# P03_MPU2_Comm.net
KiCad netlist of a schematic drawn in Altium Designer
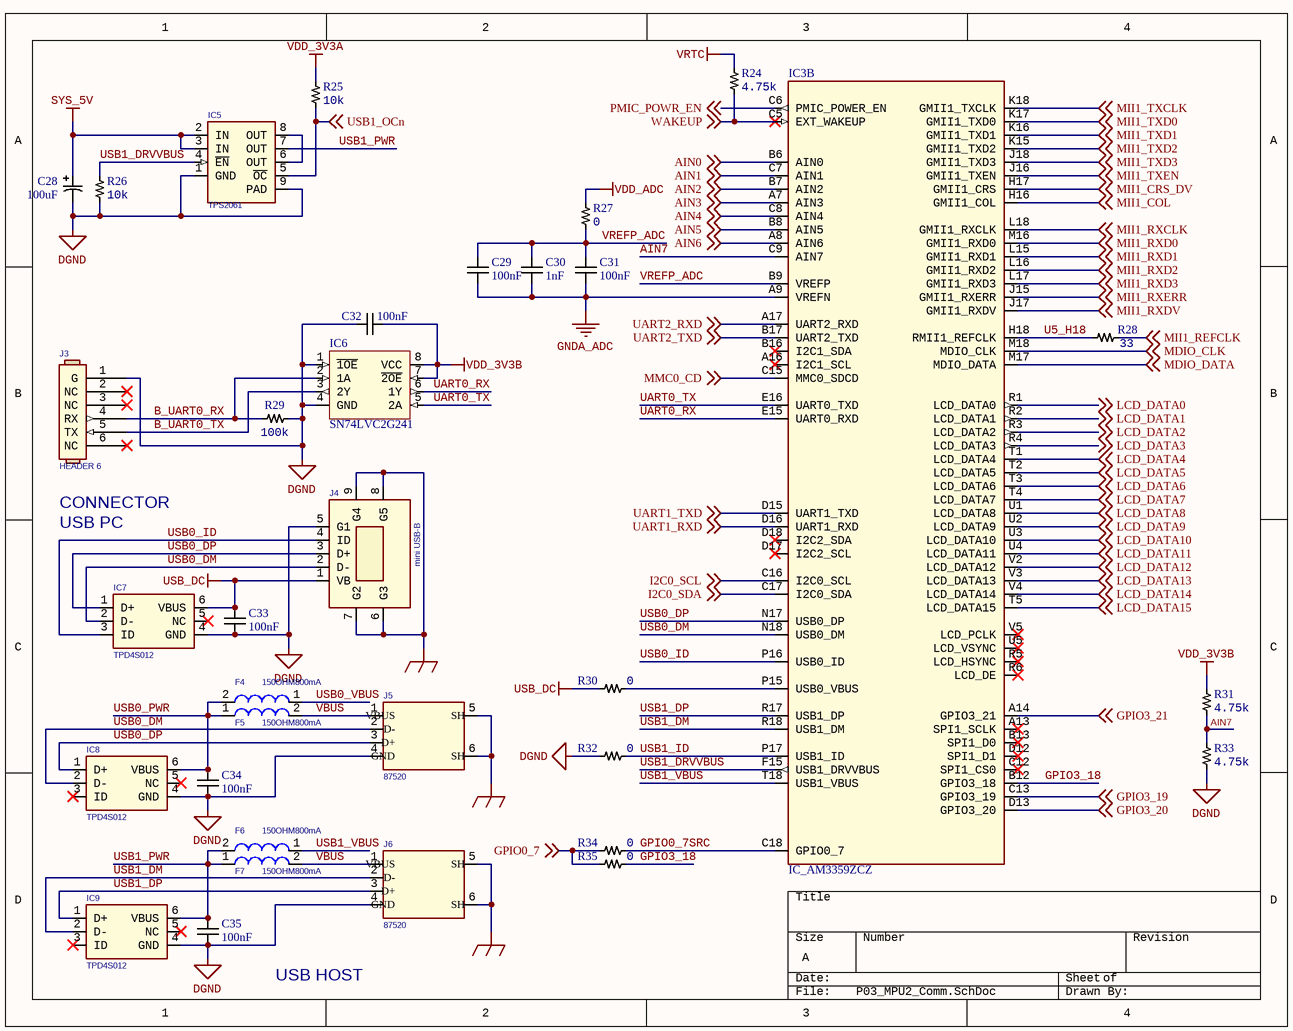
[diagram p0: P03_MPU2_Comm.SchDoc]

(export (version "E")
  (design (tool "Eeschema 10.0.6"))
  (components
    (comp (ref "C28")
      (value "EEE-0JA101SP")
      (footprint "Orient:CAP6.6x6.6")
      (description "POL CAP 100uF SMD")
      (fields
        (field (name "MANUFACTURER") "Panasonic")
        (field (name "TOLERANCE") "20%")
        (field (name "CAPACITANCE") "100uF")
      )
      (libsource (lib "Orient") (part "CAP_POL_100uF"))
    )
    (comp (ref "C29")
      (value "C0402C104K4RACTU")
      (footprint "Orient:CAP0402")
      (description "MLCC 100nF 0402 SMD")
      (fields
        (field (name "MANUFACTURER") "KEMET")
        (field (name "CAPACITANCE") "100nF")
        (field (name "TOLERANCE") "10%")
      )
      (libsource (lib "Orient") (part "CAP_100nF"))
    )
    (comp (ref "C30")
      (value "CC0402KRX7R9BB102")
      (footprint "Orient:CAP0402")
      (description "MLCC 1nF 0402 SMD")
      (fields
        (field (name "MANUFACTURER") "Yageo")
        (field (name "CAPACITANCE") "1nF")
        (field (name "TOLERANCE") "10%")
      )
      (libsource (lib "Orient") (part "CAP_1nF"))
    )
    (comp (ref "C31")
      (value "C0402C104K4RACTU")
      (footprint "Orient:CAP0402")
      (description "MLCC 100nF 0402 SMD")
      (fields
        (field (name "MANUFACTURER") "KEMET")
        (field (name "CAPACITANCE") "100nF")
        (field (name "TOLERANCE") "10%")
      )
      (libsource (lib "Orient") (part "CAP_100nF"))
    )
    (comp (ref "C32")
      (value "C0402C104K4RACTU")
      (footprint "Orient:CAP0402")
      (description "MLCC 100nF 0402 SMD")
      (fields
        (field (name "MANUFACTURER") "KEMET")
        (field (name "CAPACITANCE") "100nF")
        (field (name "TOLERANCE") "10%")
      )
      (libsource (lib "Orient") (part "CAP_100nF"))
    )
    (comp (ref "C33")
      (value "C0402C104K4RACTU")
      (footprint "Orient:CAP0402")
      (description "MLCC 100nF 0402 SMD")
      (fields
        (field (name "MANUFACTURER") "KEMET")
        (field (name "CAPACITANCE") "100nF")
        (field (name "TOLERANCE") "10%")
      )
      (libsource (lib "Orient") (part "CAP_100nF"))
    )
    (comp (ref "C34")
      (value "C0402C104K4RACTU")
      (footprint "Orient:CAP0402")
      (description "MLCC 100nF 0402 SMD")
      (fields
        (field (name "MANUFACTURER") "KEMET")
        (field (name "CAPACITANCE") "100nF")
        (field (name "TOLERANCE") "10%")
      )
      (libsource (lib "Orient") (part "CAP_100nF"))
    )
    (comp (ref "C35")
      (value "C0402C104K4RACTU")
      (footprint "Orient:CAP0402")
      (description "MLCC 100nF 0402 SMD")
      (fields
        (field (name "MANUFACTURER") "KEMET")
        (field (name "CAPACITANCE") "100nF")
        (field (name "TOLERANCE") "10%")
      )
      (libsource (lib "Orient") (part "CAP_100nF"))
    )
    (comp (ref "F4")
      (value "150OHM800mA")
      (footprint "Orient:FB0805")
      (description "FERRITE 800MA 150 OHM 0805 SMD")
      (fields
        (field (name "MANUFACTURER") "Laird-Signal Integrity Products")
        (field (name "MANUFACTURER PART NUMBER") "LI0805H151R-10")
      )
      (libsource (lib "Orient") (part "FERR"))
    )
    (comp (ref "F5")
      (value "150OHM800mA")
      (footprint "Orient:FB0805")
      (description "FERRITE 800MA 150 OHM 0805 SMD")
      (fields (field (name "MFR") "Steward") (field (name "TIINTPARTNUMBER") "1L0010"))
      (libsource (lib "") (part "FERR_1"))
    )
    (comp (ref "F6")
      (value "150OHM800mA")
      (footprint "Orient:FB0805")
      (description "FERRITE 800MA 150 OHM 0805 SMD")
      (fields
        (field (name "MANUFACTURER") "Laird-Signal Integrity Products")
        (field (name "MANUFACTURER PART NUMBER") "LI0805H151R-10")
      )
      (libsource (lib "Orient") (part "FERR"))
    )
    (comp (ref "F7")
      (value "150OHM800mA")
      (footprint "Orient:FB0805")
      (description "FERRITE 800MA 150 OHM 0805 SMD")
      (fields (field (name "MFR") "Steward") (field (name "TIINTPARTNUMBER") "1L0010"))
      (libsource (lib "") (part "FERR_1"))
    )
    (comp (ref "IC3")
      (value "IC_AM3359ZCZ")
      (footprint "Orient:BGA-324")
      (description "SubArctic Cortex A8 Processor 18x18")
      (fields
        (field (name "MANUFACTURER") "Texas Instruments")
        (field (name "MANUFACTURER PART NUMBER") "XAM3359ZCZ")
      )
      (libsource (lib "Orient") (part "IC_AM335X_ZCE_1"))
    )
    (comp (ref "IC5")
      (value "TPS2061")
      (footprint "Orient:HVSSOP-8")
      (description "IC 1.5A PWR DIST SWITCH 8-SOIC")
      (fields
        (field (name "MANUFACTURER") "Texas Instruments")
        (field (name "MANUFACTURER PART NUMBER") "TPS2051BDGNR")
      )
      (libsource (lib "Orient") (part "TPS2061"))
    )
    (comp (ref "IC6")
      (value "SN74LVC2G241")
      (footprint "Orient:VSSOP-8")
      (description "IC BUFF/DVR TRI-ST DL 8VSSOP")
      (fields
        (field (name "MANUFACTURER") "Texas Instruments")
        (field (name "MANUFACTURER PART NUMBER") "SN74LVC2G241DCUR")
      )
      (libsource (lib "Orient") (part "SN74LVC2G241"))
    )
    (comp (ref "IC7")
      (value "TPD4S012")
      (footprint "Orient:U_6_DRY")
      (description "ESD 4channel USB Interface")
      (fields (field (name "MFR") "TI") (field (name "TIINTPARTNUMBER") "1A0233"))
      (libsource (lib "Orient") (part "PROT_TPD4S012"))
    )
    (comp (ref "IC8")
      (value "TPD4S012")
      (footprint "Orient:U_6_DRY")
      (description "ESD 4channel USB Interface")
      (fields (field (name "MFR") "TI") (field (name "TIINTPARTNUMBER") "1A0233"))
      (libsource (lib "Orient") (part "PROT_TPD4S012"))
    )
    (comp (ref "IC9")
      (value "TPD4S012")
      (footprint "Orient:U_6_DRY")
      (description "ESD 4channel USB Interface")
      (fields (field (name "MFR") "TI") (field (name "TIINTPARTNUMBER") "1A0233"))
      (libsource (lib "Orient") (part "PROT_TPD4S012"))
    )
    (comp (ref "J3")
      (value "HEADER 6")
      (footprint "Orient:SIP6")
      (description "CONN HEADER 6POS, VERTICAL,  .100 STR TIN")
      (fields
        (field (name "MANUFACTURER") "Samtec Inc")
        (field (name "MANUFACTURER PART NUMBER") "FTR-110-03-G-D-06")
      )
      (libsource (lib "Orient") (part "HDR_6x1"))
    )
    (comp (ref "J4")
      (value "mini USB-B")
      (footprint "Orient:USB5MINI_4SHIELDED_SMD-5")
      (description "CONN RCPT USB MINI B R/A SMD")
      (fields (field (name "MANUFACTURER") "KYCON") (field (name "MANUFACTURER PART NUMBER") "0565790576"))
      (libsource (lib "Orient") (part "MINI-USB-AB-SOCKET"))
    )
    (comp (ref "J5")
      (value "87520")
      (footprint "Orient:USB_A")
      (description "CONN RCPT USB TYPE A R/A PCB")
      (fields (field (name "MANUFACTURER") "FCI") (field (name "MANUFACTURER PART NUMBER") "87520-0010BLF"))
      (libsource (lib "Orient") (part "CONN_USBA"))
    )
    (comp (ref "J6")
      (value "87520")
      (footprint "Orient:USB_A")
      (description "CONN RCPT USB TYPE A R/A PCB")
      (fields (field (name "MANUFACTURER") "FCI") (field (name "MANUFACTURER PART NUMBER") "87520-0010BLF"))
      (libsource (lib "Orient") (part "CONN_USBA"))
    )
    (comp (ref "R24")
      (value "RC0402FR-074K75L")
      (footprint "Orient:RES0402")
      (description "Resistor 4.75kOhm 0402 SMD")
      (fields
        (field (name "MANUFACTURER") "Yageo")
        (field (name "TOLERANCE") "1%")
        (field (name "RESISTANCE") "4.75k")
      )
      (libsource (lib "Orient") (part "RES_4.75k"))
    )
    (comp (ref "R25")
      (value "RC0402FR-0710KL")
      (footprint "Orient:RES0402")
      (description "Resistor 10kOhm 0402 SMD")
      (fields
        (field (name "MANUFACTURER") "Yageo")
        (field (name "TOLERANCE") "1%")
        (field (name "RESISTANCE") "10k")
      )
      (libsource (lib "Orient") (part "RES_10k"))
    )
    (comp (ref "R26")
      (value "RC0402FR-0710KL")
      (footprint "Orient:RES0402")
      (description "Resistor 10kOhm 0402 SMD")
      (fields
        (field (name "MANUFACTURER") "Yageo")
        (field (name "TOLERANCE") "1%")
        (field (name "RESISTANCE") "10k")
      )
      (libsource (lib "Orient") (part "RES_10k"))
    )
    (comp (ref "R27")
      (value "RC0402JR-070RL")
      (footprint "Orient:RES0402")
      (description "Resistor 0Ohm 0402 SMD")
      (fields
        (field (name "MANUFACTURER") "Yageo")
        (field (name "TOLERANCE") "5%")
        (field (name "RESISTANCE") "0")
      )
      (libsource (lib "Orient") (part "RES_0"))
    )
    (comp (ref "R28")
      (value "RC0402FR-0733RL")
      (footprint "Orient:RES0402")
      (description "Resistor 33Ohm 0402 SMD")
      (fields
        (field (name "MANUFACTURER") "Yageo")
        (field (name "TOLERANCE") "1%")
        (field (name "RESISTANCE") "33")
      )
      (libsource (lib "Orient") (part "RES_33"))
    )
    (comp (ref "R29")
      (value "RC0402FR-07100KL")
      (footprint "Orient:RES0402")
      (description "Resistor 100kOhm 0402 SMD")
      (fields
        (field (name "MANUFACTURER") "Yageo")
        (field (name "TOLERANCE") "1%")
        (field (name "RESISTANCE") "100k")
      )
      (libsource (lib "Orient") (part "RES_100k"))
    )
    (comp (ref "R30")
      (value "RC0402JR-070RL")
      (footprint "Orient:RES0402")
      (description "Resistor 0Ohm 0402 SMD")
      (fields
        (field (name "MANUFACTURER") "Yageo")
        (field (name "TOLERANCE") "5%")
        (field (name "RESISTANCE") "0")
      )
      (libsource (lib "Orient") (part "RES_0"))
    )
    (comp (ref "R31")
      (value "RC0402FR-074K75L")
      (footprint "Orient:RES0402")
      (description "Resistor 4.75kOhm 0402 SMD")
      (fields
        (field (name "MANUFACTURER") "Yageo")
        (field (name "TOLERANCE") "1%")
        (field (name "RESISTANCE") "4.75k")
      )
      (libsource (lib "Orient") (part "RES_4.75k"))
    )
    (comp (ref "R32")
      (value "RC0402JR-070RL")
      (footprint "Orient:RES0402")
      (description "Resistor 0Ohm 0402 SMD")
      (fields
        (field (name "MANUFACTURER") "Yageo")
        (field (name "TOLERANCE") "5%")
        (field (name "RESISTANCE") "0")
      )
      (libsource (lib "Orient") (part "RES_0"))
    )
    (comp (ref "R33")
      (value "RC0402FR-074K75L")
      (footprint "Orient:RES0402")
      (description "Resistor 4.75kOhm 0402 SMD")
      (fields
        (field (name "MANUFACTURER") "Yageo")
        (field (name "TOLERANCE") "1%")
        (field (name "RESISTANCE") "4.75k")
      )
      (libsource (lib "Orient") (part "RES_4.75k"))
    )
    (comp (ref "R34")
      (value "RC0402JR-070RL")
      (footprint "Orient:RES0402")
      (description "Resistor 0Ohm 0402 SMD")
      (fields
        (field (name "MANUFACTURER") "Yageo")
        (field (name "TOLERANCE") "5%")
        (field (name "RESISTANCE") "0")
      )
      (libsource (lib "Orient") (part "RES_0"))
    )
    (comp (ref "R35")
      (value "RC0402JR-070RL")
      (footprint "Orient:RES0402")
      (description "Resistor 0Ohm 0402 SMD")
      (fields
        (field (name "MANUFACTURER") "Yageo")
        (field (name "TOLERANCE") "5%")
        (field (name "RESISTANCE") "0")
      )
      (libsource (lib "Orient") (part "RES_0"))
    )
  )
  (nets
    (net (code "1") (name "/AIN7") (class "Default")
      (node (ref "IC3") (pin "C9") (pinfunction "AIN7_C9") (pintype "passive"))
      (node (ref "R31") (pin "1") (pintype "passive"))
      (node (ref "R33") (pin "2") (pintype "passive"))
    )
    (net (code "2") (name "/B_UART0_RX") (class "Default")
      (node (ref "IC6") (pin "2") (pinfunction "1A_2") (pintype "input"))
      (node (ref "J3") (pin "4") (pinfunction "RX_4") (pintype "output"))
      (node (ref "R29") (pin "2") (pintype "passive"))
    )
    (net (code "3") (name "/B_UART0_TX") (class "Default")
      (node (ref "IC6") (pin "3") (pinfunction "2Y_3") (pintype "output"))
      (node (ref "J3") (pin "5") (pinfunction "TX_5") (pintype "input"))
    )
    (net (code "4") (name "/GPIO0_7SRC") (class "Default")
      (node (ref "IC3") (pin "C18") (pinfunction "GPIO0_7_C18") (pintype "bidirectional"))
      (node (ref "R34") (pin "1") (pintype "passive"))
    )
    (net (code "5") (name "/GPIO3_18") (class "Default")
      (node (ref "IC3") (pin "B12") (pinfunction "GPIO3_18_B12") (pintype "bidirectional"))
      (node (ref "R35") (pin "2") (pintype "passive"))
    )
    (net (code "6") (name "/U5_H18") (class "Default")
      (node (ref "IC3") (pin "H18") (pinfunction "RMII1_REFCLK_H18") (pintype "bidirectional"))
      (node (ref "R28") (pin "1") (pintype "passive"))
    )
    (net (code "7") (name "/UART0_RX") (class "Default")
      (node (ref "IC3") (pin "E15") (pinfunction "UART0_RXD_E15") (pintype "bidirectional"))
      (node (ref "IC6") (pin "6") (pinfunction "1Y_6") (pintype "output"))
    )
    (net (code "8") (name "/UART0_TX") (class "Default")
      (node (ref "IC3") (pin "E16") (pinfunction "UART0_TXD_E16") (pintype "bidirectional"))
      (node (ref "IC6") (pin "5") (pinfunction "2A_5") (pintype "input"))
    )
    (net (code "9") (name "/USB0_DM") (class "Default")
      (node (ref "IC3") (pin "N18") (pinfunction "USB0_DM_N18") (pintype "bidirectional"))
      (node (ref "IC7") (pin "2") (pinfunction "D-_2") (pintype "passive"))
      (node (ref "IC8") (pin "2") (pinfunction "D-_2") (pintype "passive"))
      (node (ref "J4") (pin "2") (pinfunction "D-_2") (pintype "passive"))
      (node (ref "J5") (pin "2") (pinfunction "P2_2") (pintype "passive"))
    )
    (net (code "10") (name "/USB0_DP") (class "Default")
      (node (ref "IC3") (pin "N17") (pinfunction "USB0_DP_N17") (pintype "bidirectional"))
      (node (ref "IC7") (pin "1") (pinfunction "D+_1") (pintype "passive"))
      (node (ref "IC8") (pin "1") (pinfunction "D+_1") (pintype "passive"))
      (node (ref "J4") (pin "3") (pinfunction "D+_3") (pintype "passive"))
      (node (ref "J5") (pin "3") (pinfunction "P3_3") (pintype "passive"))
    )
    (net (code "11") (name "/USB0_ID") (class "Default")
      (node (ref "IC3") (pin "P16") (pinfunction "USB0_ID_P16") (pintype "passive"))
      (node (ref "IC7") (pin "3") (pinfunction "ID_3") (pintype "passive"))
      (node (ref "J4") (pin "4") (pinfunction "ID_4") (pintype "passive"))
    )
    (net (code "12") (name "/USB0_PWR") (class "Default")
      (node (ref "C34") (pin "1") (pintype "passive"))
      (node (ref "F4") (pin "2") (pinfunction "2_2") (pintype "passive"))
      (node (ref "F5") (pin "1") (pinfunction "1_1") (pintype "passive"))
      (node (ref "IC8") (pin "6") (pinfunction "VBUS_6") (pintype "power_in"))
    )
    (net (code "13") (name "/USB0_VBUS") (class "Default")
      (node (ref "F4") (pin "1") (pinfunction "1_1") (pintype "passive"))
    )
    (net (code "14") (name "/USB1_DM") (class "Default")
      (node (ref "IC3") (pin "R18") (pinfunction "USB1_DM_R18") (pintype "bidirectional"))
      (node (ref "IC9") (pin "2") (pinfunction "D-_2") (pintype "passive"))
      (node (ref "J6") (pin "2") (pinfunction "P2_2") (pintype "passive"))
    )
    (net (code "15") (name "/USB1_DP") (class "Default")
      (node (ref "IC3") (pin "R17") (pinfunction "USB1_DP_R17") (pintype "bidirectional"))
      (node (ref "IC9") (pin "1") (pinfunction "D+_1") (pintype "passive"))
      (node (ref "J6") (pin "3") (pinfunction "P3_3") (pintype "passive"))
    )
    (net (code "16") (name "/USB1_DRVVBUS") (class "Default")
      (node (ref "IC3") (pin "F15") (pinfunction "USB1_DRVVBUS_F15") (pintype "output"))
      (node (ref "IC5") (pin "4") (pinfunction "~{EN}_4") (pintype "input"))
      (node (ref "R26") (pin "1") (pintype "passive"))
    )
    (net (code "17") (name "/USB1_ID") (class "Default")
      (node (ref "IC3") (pin "P17") (pinfunction "USB1_ID_P17") (pintype "passive"))
      (node (ref "R32") (pin "2") (pintype "passive"))
    )
    (net (code "18") (name "/USB1_PWR") (class "Default")
      (node (ref "C35") (pin "1") (pintype "passive"))
      (node (ref "F6") (pin "2") (pinfunction "2_2") (pintype "passive"))
      (node (ref "F7") (pin "1") (pinfunction "1_1") (pintype "passive"))
      (node (ref "IC5") (pin "7") (pinfunction "OUT_7") (pintype "power_in"))
      (node (ref "IC9") (pin "6") (pinfunction "VBUS_6") (pintype "power_in"))
    )
    (net (code "19") (name "/USB1_VBUS") (class "Default")
      (node (ref "F6") (pin "1") (pinfunction "1_1") (pintype "passive"))
      (node (ref "IC3") (pin "T18") (pinfunction "USB1_VBUS_T18") (pintype "passive"))
    )
    (net (code "20") (name "/VBUS") (class "Default")
      (node (ref "F5") (pin "2") (pinfunction "2_2") (pintype "passive"))
      (node (ref "F7") (pin "2") (pinfunction "2_2") (pintype "passive"))
      (node (ref "J5") (pin "1") (pinfunction "P1_1") (pintype "passive"))
      (node (ref "J6") (pin "1") (pinfunction "P1_1") (pintype "passive"))
    )
    (net (code "21") (name "/VREFP_ADC") (class "Default")
      (node (ref "C29") (pin "1") (pintype "passive"))
      (node (ref "C30") (pin "1") (pintype "passive"))
      (node (ref "C31") (pin "1") (pintype "passive"))
      (node (ref "IC3") (pin "B9") (pinfunction "VREFP_B9") (pintype "passive"))
      (node (ref "R27") (pin "1") (pintype "passive"))
    )
    (net (code "22") (name "AIN0") (class "Default")
      (node (ref "IC3") (pin "B6") (pinfunction "AIN0_B6") (pintype "passive"))
    )
    (net (code "23") (name "AIN1") (class "Default")
      (node (ref "IC3") (pin "C7") (pinfunction "AIN1_C7") (pintype "passive"))
    )
    (net (code "24") (name "AIN2") (class "Default")
      (node (ref "IC3") (pin "B7") (pinfunction "AIN2_B7") (pintype "passive"))
    )
    (net (code "25") (name "AIN3") (class "Default")
      (node (ref "IC3") (pin "A7") (pinfunction "AIN3_A7") (pintype "passive"))
    )
    (net (code "26") (name "AIN4") (class "Default")
      (node (ref "IC3") (pin "C8") (pinfunction "AIN4_C8") (pintype "passive"))
    )
    (net (code "27") (name "AIN5") (class "Default")
      (node (ref "IC3") (pin "B8") (pinfunction "AIN5_B8") (pintype "passive"))
    )
    (net (code "28") (name "AIN6") (class "Default")
      (node (ref "IC3") (pin "A8") (pinfunction "AIN6_A8") (pintype "passive"))
    )
    (net (code "29") (name "DGND") (class "Default")
      (node (ref "C28") (pin "2") (pinfunction "C_2") (pintype "passive"))
      (node (ref "C32") (pin "1") (pintype "passive"))
      (node (ref "C33") (pin "2") (pintype "passive"))
      (node (ref "C34") (pin "2") (pintype "passive"))
      (node (ref "C35") (pin "2") (pintype "passive"))
      (node (ref "IC5") (pin "1") (pinfunction "GND_1") (pintype "power_in"))
      (node (ref "IC5") (pin "9") (pinfunction "PAD_9") (pintype "passive"))
      (node (ref "IC6") (pin "1") (pinfunction "~{1OE}_1") (pintype "input"))
      (node (ref "IC6") (pin "4") (pinfunction "GND_4") (pintype "power_in"))
      (node (ref "IC7") (pin "4") (pinfunction "GND_4") (pintype "power_in"))
      (node (ref "IC8") (pin "4") (pinfunction "GND_4") (pintype "power_in"))
      (node (ref "IC9") (pin "4") (pinfunction "GND_4") (pintype "power_in"))
      (node (ref "J3") (pin "1") (pinfunction "G_1") (pintype "power_in"))
      (node (ref "J4") (pin "5") (pinfunction "G1_5") (pintype "passive"))
      (node (ref "J5") (pin "4") (pinfunction "P4_4") (pintype "passive"))
      (node (ref "J6") (pin "4") (pinfunction "P4_4") (pintype "passive"))
      (node (ref "R26") (pin "2") (pintype "passive"))
      (node (ref "R29") (pin "1") (pintype "passive"))
      (node (ref "R32") (pin "1") (pintype "passive"))
      (node (ref "R33") (pin "1") (pintype "passive"))
    )
    (net (code "30") (name "GNDA_ADC") (class "Default")
      (node (ref "C29") (pin "2") (pintype "passive"))
      (node (ref "C30") (pin "2") (pintype "passive"))
      (node (ref "C31") (pin "2") (pintype "passive"))
      (node (ref "IC3") (pin "A9") (pinfunction "VREFN_A9") (pintype "passive"))
    )
    (net (code "31") (name "GND_EARTH") (class "Default")
      (node (ref "J4") (pin "6") (pinfunction "G3_6") (pintype "passive"))
      (node (ref "J4") (pin "7") (pinfunction "G2_7") (pintype "passive"))
      (node (ref "J4") (pin "8") (pinfunction "G5_8") (pintype "passive"))
      (node (ref "J4") (pin "9") (pinfunction "G4_9") (pintype "passive"))
      (node (ref "J5") (pin "5") (pinfunction "SHELD1_5") (pintype "passive"))
      (node (ref "J5") (pin "6") (pinfunction "PAD4_6") (pintype "passive"))
      (node (ref "J6") (pin "5") (pinfunction "SHELD1_5") (pintype "passive"))
      (node (ref "J6") (pin "6") (pinfunction "PAD4_6") (pintype "passive"))
    )
    (net (code "32") (name "GPIO0_7") (class "Default")
      (node (ref "R34") (pin "2") (pintype "passive"))
      (node (ref "R35") (pin "1") (pintype "passive"))
    )
    (net (code "33") (name "GPIO3_19") (class "Default")
      (node (ref "IC3") (pin "C13") (pinfunction "GPIO3_19_C13") (pintype "bidirectional"))
    )
    (net (code "34") (name "GPIO3_20") (class "Default")
      (node (ref "IC3") (pin "D13") (pinfunction "GPIO3_20_D13") (pintype "bidirectional"))
    )
    (net (code "35") (name "GPIO3_21") (class "Default")
      (node (ref "IC3") (pin "A14") (pinfunction "GPIO3_21_A14") (pintype "bidirectional"))
    )
    (net (code "36") (name "I2C0_SCL") (class "Default")
      (node (ref "IC3") (pin "C16") (pinfunction "I2C0_SCL_C16") (pintype "bidirectional"))
    )
    (net (code "37") (name "I2C0_SDA") (class "Default")
      (node (ref "IC3") (pin "C17") (pinfunction "I2C0_SDA_C17") (pintype "bidirectional"))
    )
    (net (code "38") (name "LCD_DATA0") (class "Default")
      (node (ref "IC3") (pin "R1") (pinfunction "LCD_DATA0_R1") (pintype "output"))
    )
    (net (code "39") (name "LCD_DATA1") (class "Default")
      (node (ref "IC3") (pin "R2") (pinfunction "LCD_DATA1_R2") (pintype "output"))
    )
    (net (code "40") (name "LCD_DATA2") (class "Default")
      (node (ref "IC3") (pin "R3") (pinfunction "LCD_DATA2_R3") (pintype "output"))
    )
    (net (code "41") (name "LCD_DATA3") (class "Default")
      (node (ref "IC3") (pin "R4") (pinfunction "LCD_DATA3_R4") (pintype "output"))
    )
    (net (code "42") (name "LCD_DATA4") (class "Default")
      (node (ref "IC3") (pin "T1") (pinfunction "LCD_DATA4_T1") (pintype "bidirectional"))
    )
    (net (code "43") (name "LCD_DATA5") (class "Default")
      (node (ref "IC3") (pin "T2") (pinfunction "LCD_DATA5_T2") (pintype "bidirectional"))
    )
    (net (code "44") (name "LCD_DATA6") (class "Default")
      (node (ref "IC3") (pin "T3") (pinfunction "LCD_DATA6_T3") (pintype "bidirectional"))
    )
    (net (code "45") (name "LCD_DATA7") (class "Default")
      (node (ref "IC3") (pin "T4") (pinfunction "LCD_DATA7_T4") (pintype "bidirectional"))
    )
    (net (code "46") (name "LCD_DATA8") (class "Default")
      (node (ref "IC3") (pin "U1") (pinfunction "LCD_DATA8_U1") (pintype "bidirectional"))
    )
    (net (code "47") (name "LCD_DATA9") (class "Default")
      (node (ref "IC3") (pin "U2") (pinfunction "LCD_DATA9_U2") (pintype "bidirectional"))
    )
    (net (code "48") (name "LCD_DATA10") (class "Default")
      (node (ref "IC3") (pin "U3") (pinfunction "LCD_DATA10_U3") (pintype "bidirectional"))
    )
    (net (code "49") (name "LCD_DATA11") (class "Default")
      (node (ref "IC3") (pin "U4") (pinfunction "LCD_DATA11_U4") (pintype "bidirectional"))
    )
    (net (code "50") (name "LCD_DATA12") (class "Default")
      (node (ref "IC3") (pin "V2") (pinfunction "LCD_DATA12_V2") (pintype "bidirectional"))
    )
    (net (code "51") (name "LCD_DATA13") (class "Default")
      (node (ref "IC3") (pin "V3") (pinfunction "LCD_DATA13_V3") (pintype "bidirectional"))
    )
    (net (code "52") (name "LCD_DATA14") (class "Default")
      (node (ref "IC3") (pin "V4") (pinfunction "LCD_DATA14_V4") (pintype "bidirectional"))
    )
    (net (code "53") (name "LCD_DATA15") (class "Default")
      (node (ref "IC3") (pin "T5") (pinfunction "LCD_DATA15_T5") (pintype "bidirectional"))
    )
    (net (code "54") (name "MDIO_CLK") (class "Default")
      (node (ref "IC3") (pin "M18") (pinfunction "MDIO_CLK_M18") (pintype "bidirectional"))
    )
    (net (code "55") (name "MDIO_DATA") (class "Default")
      (node (ref "IC3") (pin "M17") (pinfunction "MDIO_DATA_M17") (pintype "bidirectional"))
    )
    (net (code "56") (name "MII1_COL") (class "Default")
      (node (ref "IC3") (pin "H16") (pinfunction "GMII1_COL_H16") (pintype "bidirectional"))
    )
    (net (code "57") (name "MII1_CRS_DV") (class "Default")
      (node (ref "IC3") (pin "H17") (pinfunction "GMII1_CRS_H17") (pintype "bidirectional"))
    )
    (net (code "58") (name "MII1_REFCLK") (class "Default") (node (ref "R28") (pin "2") (pintype "passive")))
    (net (code "59") (name "MII1_RXCLK") (class "Default")
      (node (ref "IC3") (pin "L18") (pinfunction "GMII1_RXCLK_L18") (pintype "bidirectional"))
    )
    (net (code "60") (name "MII1_RXD0") (class "Default")
      (node (ref "IC3") (pin "M16") (pinfunction "GMII1_RXD0_M16") (pintype "passive"))
    )
    (net (code "61") (name "MII1_RXD1") (class "Default")
      (node (ref "IC3") (pin "L15") (pinfunction "GMII1_RXD1_L15") (pintype "bidirectional"))
    )
    (net (code "62") (name "MII1_RXD2") (class "Default")
      (node (ref "IC3") (pin "L16") (pinfunction "GMII1_RXD2_L16") (pintype "bidirectional"))
    )
    (net (code "63") (name "MII1_RXD3") (class "Default")
      (node (ref "IC3") (pin "L17") (pinfunction "GMII1_RXD3_L17") (pintype "bidirectional"))
    )
    (net (code "64") (name "MII1_RXDV") (class "Default")
      (node (ref "IC3") (pin "J17") (pinfunction "GMII1_RXDV_J17") (pintype "bidirectional"))
    )
    (net (code "65") (name "MII1_RXERR") (class "Default")
      (node (ref "IC3") (pin "J15") (pinfunction "GMII1_RXERR_J15") (pintype "bidirectional"))
    )
    (net (code "66") (name "MII1_TXCLK") (class "Default")
      (node (ref "IC3") (pin "K18") (pinfunction "GMII1_TXCLK_K18") (pintype "bidirectional"))
    )
    (net (code "67") (name "MII1_TXD0") (class "Default")
      (node (ref "IC3") (pin "K17") (pinfunction "GMII1_TXD0_K17") (pintype "bidirectional"))
    )
    (net (code "68") (name "MII1_TXD1") (class "Default")
      (node (ref "IC3") (pin "K16") (pinfunction "GMII1_TXD1_K16") (pintype "bidirectional"))
    )
    (net (code "69") (name "MII1_TXD2") (class "Default")
      (node (ref "IC3") (pin "K15") (pinfunction "GMII1_TXD2_K15") (pintype "bidirectional"))
    )
    (net (code "70") (name "MII1_TXD3") (class "Default")
      (node (ref "IC3") (pin "J18") (pinfunction "GMII1_TXD3_J18") (pintype "bidirectional"))
    )
    (net (code "71") (name "MII1_TXEN") (class "Default")
      (node (ref "IC3") (pin "J16") (pinfunction "GMII1_TXEN_J16") (pintype "bidirectional"))
    )
    (net (code "72") (name "MMC0_CD") (class "Default")
      (node (ref "IC3") (pin "C15") (pinfunction "MMC0_SDCD_C15") (pintype "bidirectional"))
    )
    (net (code "73") (name "Net-(IC3B-USB0_VBUS)") (class "Default")
      (node (ref "IC3") (pin "P15") (pinfunction "USB0_VBUS_P15") (pintype "passive"))
      (node (ref "R30") (pin "2") (pintype "passive"))
    )
    (net (code "74") (name "Net-(IC5-OUT-Pad6)") (class "Default")
      (node (ref "IC5") (pin "6") (pinfunction "OUT_6") (pintype "power_in"))
      (node (ref "IC5") (pin "8") (pinfunction "OUT_8") (pintype "power_in"))
    )
    (net (code "75") (name "PMIC_POWR_EN") (class "Default")
      (node (ref "IC3") (pin "C6") (pinfunction "PMIC_POWER_EN_C6") (pintype "output"))
    )
    (net (code "76") (name "SYS_5V") (class "Default")
      (node (ref "C28") (pin "1") (pinfunction "A_1") (pintype "passive"))
      (node (ref "IC5") (pin "2") (pinfunction "IN_2") (pintype "power_in"))
      (node (ref "IC5") (pin "3") (pinfunction "IN_3") (pintype "power_in"))
    )
    (net (code "77") (name "UART1_RXD") (class "Default")
      (node (ref "IC3") (pin "D16") (pinfunction "UART1_RXD_D16") (pintype "bidirectional"))
    )
    (net (code "78") (name "UART1_TXD") (class "Default")
      (node (ref "IC3") (pin "D15") (pinfunction "UART1_TXD_D15") (pintype "bidirectional"))
    )
    (net (code "79") (name "UART2_RXD") (class "Default")
      (node (ref "IC3") (pin "A17") (pinfunction "UART2_RXD_A17") (pintype "bidirectional"))
    )
    (net (code "80") (name "UART2_TXD") (class "Default")
      (node (ref "IC3") (pin "B17") (pinfunction "UART2_TXD_B17") (pintype "bidirectional"))
    )
    (net (code "81") (name "USB1_OCn") (class "Default")
      (node (ref "IC5") (pin "5") (pinfunction "~{OC}_5") (pintype "passive"))
      (node (ref "R25") (pin "2") (pintype "passive"))
    )
    (net (code "82") (name "USB_DC") (class "Default")
      (node (ref "C33") (pin "1") (pintype "passive"))
      (node (ref "IC7") (pin "6") (pinfunction "VBUS_6") (pintype "power_in"))
      (node (ref "J4") (pin "1") (pinfunction "VB_1") (pintype "passive"))
      (node (ref "R30") (pin "1") (pintype "passive"))
    )
    (net (code "83") (name "VDD_3V3A") (class "Default") (node (ref "R25") (pin "1") (pintype "passive")))
    (net (code "84") (name "VDD_3V3B") (class "Default")
      (node (ref "C32") (pin "2") (pintype "passive"))
      (node (ref "IC6") (pin "7") (pinfunction "~{2OE}_7") (pintype "input"))
      (node (ref "IC6") (pin "8") (pinfunction "VCC_8") (pintype "power_in"))
      (node (ref "R31") (pin "2") (pintype "passive"))
    )
    (net (code "85") (name "VDD_ADC") (class "Default") (node (ref "R27") (pin "2") (pintype "passive")))
    (net (code "86") (name "VRTC") (class "Default") (node (ref "R24") (pin "2") (pintype "passive")))
    (net (code "87") (name "WAKEUP") (class "Default")
      (node (ref "IC3") (pin "C5") (pinfunction "EXT_WAKEUP_C5") (pintype "input"))
      (node (ref "R24") (pin "1") (pintype "passive"))
    )
    (net (code "88") (name "unconnected-(IC3B-I2C1_SCL-PadA16)") (class "Default")
      (node (ref "IC3") (pin "A16") (pinfunction "I2C1_SCL_A16") (pintype "bidirectional+no_connect"))
    )
    (net (code "89") (name "unconnected-(IC3B-I2C1_SDA-PadB16)") (class "Default")
      (node (ref "IC3") (pin "B16") (pinfunction "I2C1_SDA_B16") (pintype "bidirectional+no_connect"))
    )
    (net (code "90") (name "unconnected-(IC3B-I2C2_SCL-PadD17)") (class "Default")
      (node (ref "IC3") (pin "D17") (pinfunction "I2C2_SCL_D17") (pintype "bidirectional+no_connect"))
    )
    (net (code "91") (name "unconnected-(IC3B-I2C2_SDA-PadD18)") (class "Default")
      (node (ref "IC3") (pin "D18") (pinfunction "I2C2_SDA_D18") (pintype "bidirectional+no_connect"))
    )
    (net (code "92") (name "unconnected-(IC3B-LCD_DE-PadR6)") (class "Default")
      (node (ref "IC3") (pin "R6") (pinfunction "LCD_DE_R6") (pintype "bidirectional+no_connect"))
    )
    (net (code "93") (name "unconnected-(IC3B-LCD_HSYNC-PadR5)") (class "Default")
      (node (ref "IC3") (pin "R5") (pinfunction "LCD_HSYNC_R5") (pintype "bidirectional+no_connect"))
    )
    (net (code "94") (name "unconnected-(IC3B-LCD_PCLK-PadV5)") (class "Default")
      (node (ref "IC3") (pin "V5") (pinfunction "LCD_PCLK_V5") (pintype "bidirectional+no_connect"))
    )
    (net (code "95") (name "unconnected-(IC3B-LCD_VSYNC-PadU5)") (class "Default")
      (node (ref "IC3") (pin "U5") (pinfunction "LCD_VSYNC_U5") (pintype "bidirectional+no_connect"))
    )
    (net (code "96") (name "unconnected-(IC3B-SPI1_CS0-PadC12)") (class "Default")
      (node (ref "IC3") (pin "C12") (pinfunction "SPI1_CS0_C12") (pintype "bidirectional+no_connect"))
    )
    (net (code "97") (name "unconnected-(IC3B-SPI1_D0-PadB13)") (class "Default")
      (node (ref "IC3") (pin "B13") (pinfunction "SPI1_D0_B13") (pintype "bidirectional+no_connect"))
    )
    (net (code "98") (name "unconnected-(IC3B-SPI1_D1-PadD12)") (class "Default")
      (node (ref "IC3") (pin "D12") (pinfunction "SPI1_D1_D12") (pintype "bidirectional+no_connect"))
    )
    (net (code "99") (name "unconnected-(IC3B-SPI1_SCLK-PadA13)") (class "Default")
      (node (ref "IC3") (pin "A13") (pinfunction "SPI1_SCLK_A13") (pintype "bidirectional+no_connect"))
    )
    (net (code "100") (name "unconnected-(IC7-NC-Pad5)") (class "Default")
      (node (ref "IC7") (pin "5") (pinfunction "NC_5") (pintype "passive+no_connect"))
    )
    (net (code "101") (name "unconnected-(IC8-ID-Pad3)") (class "Default")
      (node (ref "IC8") (pin "3") (pinfunction "ID_3") (pintype "passive+no_connect"))
    )
    (net (code "102") (name "unconnected-(IC8-NC-Pad5)") (class "Default")
      (node (ref "IC8") (pin "5") (pinfunction "NC_5") (pintype "passive+no_connect"))
    )
    (net (code "103") (name "unconnected-(IC9-ID-Pad3)") (class "Default")
      (node (ref "IC9") (pin "3") (pinfunction "ID_3") (pintype "passive+no_connect"))
    )
    (net (code "104") (name "unconnected-(IC9-NC-Pad5)") (class "Default")
      (node (ref "IC9") (pin "5") (pinfunction "NC_5") (pintype "passive+no_connect"))
    )
    (net (code "105") (name "unconnected-(J3-NC-Pad2)") (class "Default")
      (node (ref "J3") (pin "2") (pinfunction "NC_2") (pintype "passive+no_connect"))
    )
    (net (code "106") (name "unconnected-(J3-NC-Pad3)") (class "Default")
      (node (ref "J3") (pin "3") (pinfunction "NC_3") (pintype "passive+no_connect"))
    )
    (net (code "107") (name "unconnected-(J3-NC-Pad6)") (class "Default")
      (node (ref "J3") (pin "6") (pinfunction "NC_6") (pintype "passive+no_connect"))
    )
  )
)
